# carrier_card_s3.net
KiCad netlist of a schematic drawn in Altium Designer
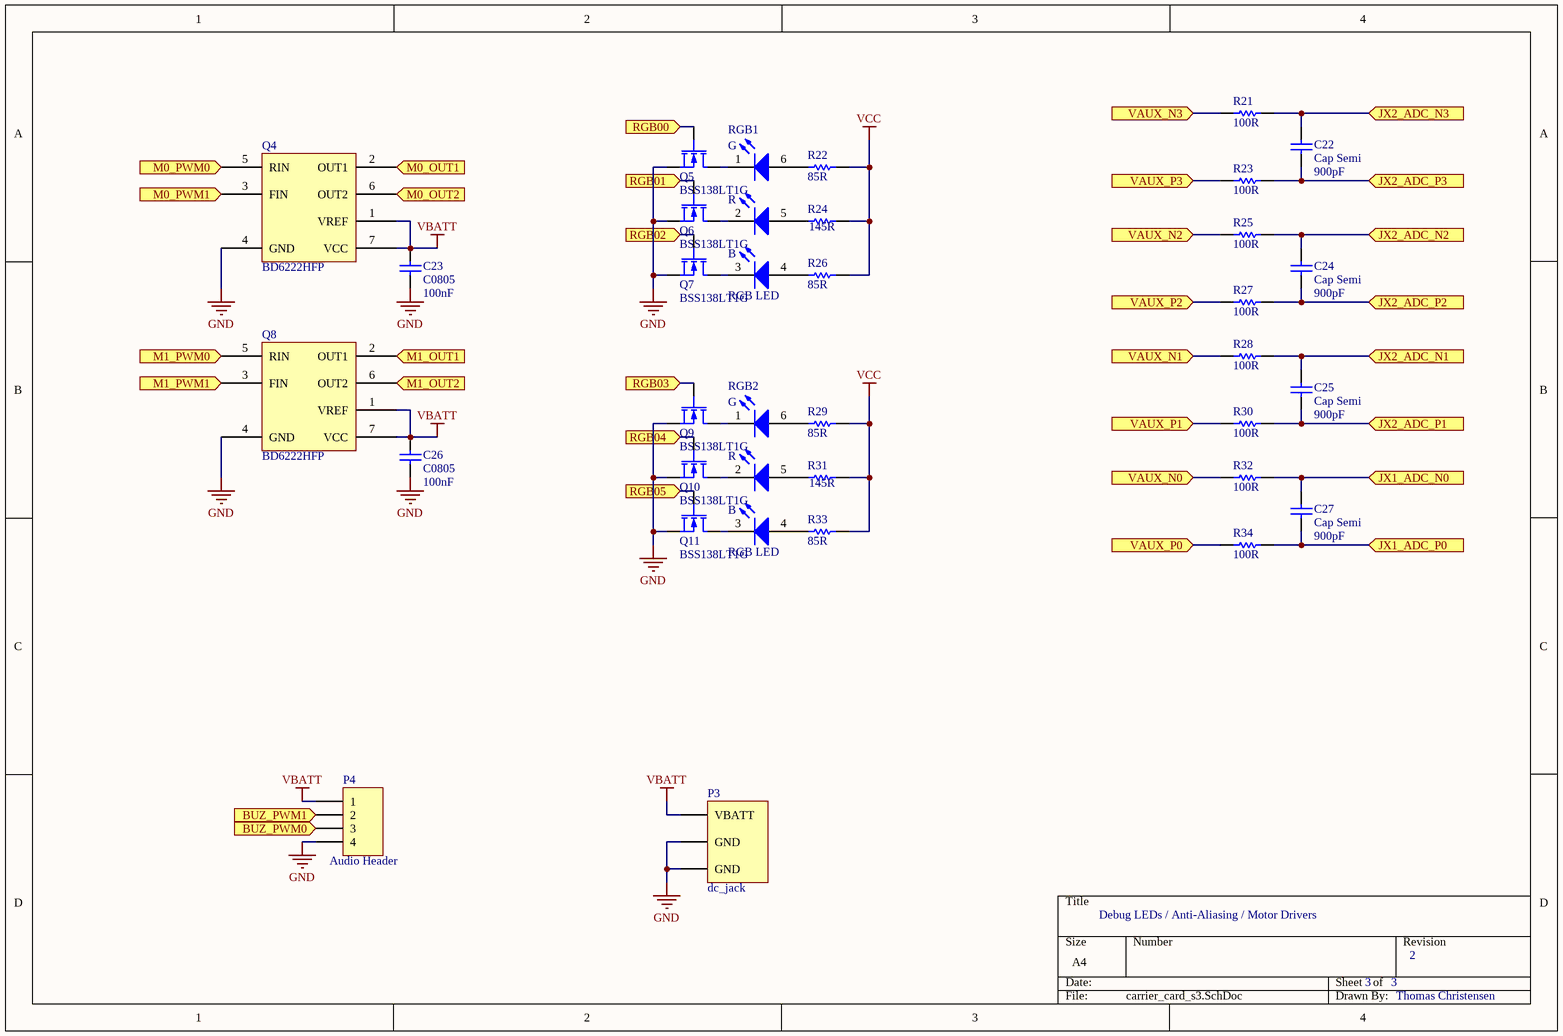
[diagram p0: carrier_card_s3.SchDoc]

(export (version "E")
  (design (tool "Eeschema 10.0.6"))
  (components
    (comp (ref "C22")
      (value "Cap Semi")
      (footprint "0402")
      (description "Capacitor (Semiconductor SIM Model)")
      (fields (field (name "ALTIUM_VALUE") "900pF") (field (name "PUBLISHER") "Altium Limited"))
      (libsource (lib "Miscellaneous Devices") (part "Cap Semi"))
    )
    (comp (ref "C23")
      (value "C0805")
      (footprint "0805")
      (description "Ceramic Chip Capacitor - Standard")
      (fields (field (name "ALTIUM_VALUE") "100nF") (field (name "PUBLISHER") "Altium Limited"))
      (libsource (lib "KEMET Chip Capacitor") (part "C0805"))
    )
    (comp (ref "C24")
      (value "Cap Semi")
      (footprint "0402")
      (description "Capacitor (Semiconductor SIM Model)")
      (fields (field (name "ALTIUM_VALUE") "900pF") (field (name "PUBLISHER") "Altium Limited"))
      (libsource (lib "Miscellaneous Devices") (part "Cap Semi"))
    )
    (comp (ref "C25")
      (value "Cap Semi")
      (footprint "0402")
      (description "Capacitor (Semiconductor SIM Model)")
      (fields (field (name "ALTIUM_VALUE") "900pF") (field (name "PUBLISHER") "Altium Limited"))
      (libsource (lib "Miscellaneous Devices") (part "Cap Semi"))
    )
    (comp (ref "C26")
      (value "C0805")
      (footprint "0805")
      (description "Ceramic Chip Capacitor - Standard")
      (fields (field (name "ALTIUM_VALUE") "100nF") (field (name "PUBLISHER") "Altium Limited"))
      (libsource (lib "KEMET Chip Capacitor") (part "C0805"))
    )
    (comp (ref "C27")
      (value "Cap Semi")
      (footprint "0402")
      (description "Capacitor (Semiconductor SIM Model)")
      (fields (field (name "ALTIUM_VALUE") "900pF") (field (name "PUBLISHER") "Altium Limited"))
      (libsource (lib "Miscellaneous Devices") (part "Cap Semi"))
    )
    (comp (ref "P3")
      (value "dc_jack")
      (footprint "Power Jack")
      (libsource (lib "swarmbot_schematic_library") (part "dc_jack"))
    )
    (comp (ref "P4")
      (value "Audio Header")
      (footprint "HDR1X4")
      (description "Header, 4-Pin")
      (fields (field (name "PUBLISHER") "Altium Limited"))
      (libsource (lib "Miscellaneous Connectors") (part "Header 4"))
    )
    (comp (ref "Q4")
      (value "BD6222HFP")
      (footprint "HRP7_N")
      (libsource (lib "swarmbot_schematic_library") (part "BD6222HFP"))
    )
    (comp (ref "Q5")
      (value "BSS138LT1G")
      (footprint "SOT-23B")
      (description "N-Channel MOSFET")
      (fields (field (name "PUBLISHER") "Altium Limited"))
      (libsource (lib "swarmbot_schematic_library") (part "BSS138LT1G"))
    )
    (comp (ref "Q6")
      (value "BSS138LT1G")
      (footprint "SOT-23B")
      (description "N-Channel MOSFET")
      (fields (field (name "PUBLISHER") "Altium Limited"))
      (libsource (lib "swarmbot_schematic_library") (part "BSS138LT1G"))
    )
    (comp (ref "Q7")
      (value "BSS138LT1G")
      (footprint "SOT-23B")
      (description "N-Channel MOSFET")
      (fields (field (name "PUBLISHER") "Altium Limited"))
      (libsource (lib "swarmbot_schematic_library") (part "BSS138LT1G"))
    )
    (comp (ref "Q8")
      (value "BD6222HFP")
      (footprint "HRP7_N")
      (libsource (lib "swarmbot_schematic_library") (part "BD6222HFP"))
    )
    (comp (ref "Q9")
      (value "BSS138LT1G")
      (footprint "SOT-23B")
      (description "N-Channel MOSFET")
      (fields (field (name "PUBLISHER") "Altium Limited"))
      (libsource (lib "swarmbot_schematic_library") (part "BSS138LT1G"))
    )
    (comp (ref "Q10")
      (value "BSS138LT1G")
      (footprint "SOT-23B")
      (description "N-Channel MOSFET")
      (fields (field (name "PUBLISHER") "Altium Limited"))
      (libsource (lib "swarmbot_schematic_library") (part "BSS138LT1G"))
    )
    (comp (ref "Q11")
      (value "BSS138LT1G")
      (footprint "SOT-23B")
      (description "N-Channel MOSFET")
      (fields (field (name "PUBLISHER") "Altium Limited"))
      (libsource (lib "swarmbot_schematic_library") (part "BSS138LT1G"))
    )
    (comp (ref "R21")
      (value "100R")
      (footprint "2-0402")
      (description "Thick Film Chip Resistor, 1 Ohm to 2.2M Ohm Range, 5% Tolerance, 0402 Size, 0.063 W")
      (fields (field (name "PUBLISHER") "Altium Limited"))
      (libsource (lib "Panasonic Resistor") (part "ERJ2GE"))
    )
    (comp (ref "R22")
      (value "85R")
      (footprint "ERA-0603")
      (fields (field (name "PUBLISHER") "Altium Limited"))
      (libsource (lib "Panasonic Resistor") (part "ERA3Y"))
    )
    (comp (ref "R23")
      (value "100R")
      (footprint "2-0402")
      (description "Thick Film Chip Resistor, 1 Ohm to 2.2M Ohm Range, 5% Tolerance, 0402 Size, 0.063 W")
      (fields (field (name "PUBLISHER") "Altium Limited"))
      (libsource (lib "Panasonic Resistor") (part "ERJ2GE"))
    )
    (comp (ref "R24")
      (value "145R")
      (footprint "ERA-0603")
      (fields (field (name "PUBLISHER") "Altium Limited"))
      (libsource (lib "Panasonic Resistor") (part "ERA3Y"))
    )
    (comp (ref "R25")
      (value "100R")
      (footprint "2-0402")
      (description "Thick Film Chip Resistor, 1 Ohm to 2.2M Ohm Range, 5% Tolerance, 0402 Size, 0.063 W")
      (fields (field (name "PUBLISHER") "Altium Limited"))
      (libsource (lib "Panasonic Resistor") (part "ERJ2GE"))
    )
    (comp (ref "R26")
      (value "85R")
      (footprint "ERA-0603")
      (fields (field (name "PUBLISHER") "Altium Limited"))
      (libsource (lib "Panasonic Resistor") (part "ERA3Y"))
    )
    (comp (ref "R27")
      (value "100R")
      (footprint "2-0402")
      (description "Thick Film Chip Resistor, 1 Ohm to 2.2M Ohm Range, 5% Tolerance, 0402 Size, 0.063 W")
      (fields (field (name "PUBLISHER") "Altium Limited"))
      (libsource (lib "Panasonic Resistor") (part "ERJ2GE"))
    )
    (comp (ref "R28")
      (value "100R")
      (footprint "2-0402")
      (description "Thick Film Chip Resistor, 1 Ohm to 2.2M Ohm Range, 5% Tolerance, 0402 Size, 0.063 W")
      (fields (field (name "PUBLISHER") "Altium Limited"))
      (libsource (lib "Panasonic Resistor") (part "ERJ2GE"))
    )
    (comp (ref "R29")
      (value "85R")
      (footprint "ERA-0603")
      (fields (field (name "PUBLISHER") "Altium Limited"))
      (libsource (lib "Panasonic Resistor") (part "ERA3Y"))
    )
    (comp (ref "R30")
      (value "100R")
      (footprint "2-0402")
      (description "Thick Film Chip Resistor, 1 Ohm to 2.2M Ohm Range, 5% Tolerance, 0402 Size, 0.063 W")
      (fields (field (name "PUBLISHER") "Altium Limited"))
      (libsource (lib "Panasonic Resistor") (part "ERJ2GE"))
    )
    (comp (ref "R31")
      (value "145R")
      (footprint "ERA-0603")
      (fields (field (name "PUBLISHER") "Altium Limited"))
      (libsource (lib "Panasonic Resistor") (part "ERA3Y"))
    )
    (comp (ref "R32")
      (value "100R")
      (footprint "2-0402")
      (description "Thick Film Chip Resistor, 1 Ohm to 2.2M Ohm Range, 5% Tolerance, 0402 Size, 0.063 W")
      (fields (field (name "PUBLISHER") "Altium Limited"))
      (libsource (lib "Panasonic Resistor") (part "ERJ2GE"))
    )
    (comp (ref "R33")
      (value "85R")
      (footprint "ERA-0603")
      (fields (field (name "PUBLISHER") "Altium Limited"))
      (libsource (lib "Panasonic Resistor") (part "ERA3Y"))
    )
    (comp (ref "R34")
      (value "100R")
      (footprint "2-0402")
      (description "Thick Film Chip Resistor, 1 Ohm to 2.2M Ohm Range, 5% Tolerance, 0402 Size, 0.063 W")
      (fields (field (name "PUBLISHER") "Altium Limited"))
      (libsource (lib "Panasonic Resistor") (part "ERJ2GE"))
    )
    (comp (ref "RGB1")
      (value "RGB LED")
      (footprint "RGB_LED")
      (libsource (lib "swarmbot_schematic_library") (part "LTRB R8SF"))
    )
    (comp (ref "RGB2")
      (value "RGB LED")
      (footprint "RGB_LED")
      (libsource (lib "swarmbot_schematic_library") (part "LTRB R8SF"))
    )
  )
  (nets
    (net (code "1") (name "/BUZ_PWM0") (class "Default")
      (node (ref "P4") (pin "3") (pinfunction "3_3") (pintype "passive"))
    )
    (net (code "2") (name "/BUZ_PWM1") (class "Default")
      (node (ref "P4") (pin "2") (pinfunction "2_2") (pintype "passive"))
    )
    (net (code "3") (name "/JX1_ADC_N0") (class "Default")
      (node (ref "C27") (pin "2") (pinfunction "2_2") (pintype "passive"))
      (node (ref "R32") (pin "2") (pinfunction "2_2") (pintype "passive"))
    )
    (net (code "4") (name "/JX1_ADC_P0") (class "Default")
      (node (ref "C27") (pin "1") (pinfunction "1_1") (pintype "passive"))
      (node (ref "R34") (pin "2") (pinfunction "2_2") (pintype "passive"))
    )
    (net (code "5") (name "/JX2_ADC_N1") (class "Default")
      (node (ref "C25") (pin "2") (pinfunction "2_2") (pintype "passive"))
      (node (ref "R28") (pin "2") (pinfunction "2_2") (pintype "passive"))
    )
    (net (code "6") (name "/JX2_ADC_N2") (class "Default")
      (node (ref "C24") (pin "2") (pinfunction "2_2") (pintype "passive"))
      (node (ref "R25") (pin "2") (pinfunction "2_2") (pintype "passive"))
    )
    (net (code "7") (name "/JX2_ADC_N3") (class "Default")
      (node (ref "C22") (pin "2") (pinfunction "2_2") (pintype "passive"))
      (node (ref "R21") (pin "2") (pinfunction "2_2") (pintype "passive"))
    )
    (net (code "8") (name "/JX2_ADC_P1") (class "Default")
      (node (ref "C25") (pin "1") (pinfunction "1_1") (pintype "passive"))
      (node (ref "R30") (pin "2") (pinfunction "2_2") (pintype "passive"))
    )
    (net (code "9") (name "/JX2_ADC_P2") (class "Default")
      (node (ref "C24") (pin "1") (pinfunction "1_1") (pintype "passive"))
      (node (ref "R27") (pin "2") (pinfunction "2_2") (pintype "passive"))
    )
    (net (code "10") (name "/JX2_ADC_P3") (class "Default")
      (node (ref "C22") (pin "1") (pinfunction "1_1") (pintype "passive"))
      (node (ref "R23") (pin "2") (pinfunction "2_2") (pintype "passive"))
    )
    (net (code "11") (name "/M0_OUT1") (class "Default")
      (node (ref "Q4") (pin "2") (pinfunction "OUT1_2") (pintype "passive"))
    )
    (net (code "12") (name "/M0_OUT2") (class "Default")
      (node (ref "Q4") (pin "6") (pinfunction "OUT2_6") (pintype "passive"))
    )
    (net (code "13") (name "/M0_PWM0") (class "Default")
      (node (ref "Q4") (pin "5") (pinfunction "RIN_5") (pintype "passive"))
    )
    (net (code "14") (name "/M0_PWM1") (class "Default")
      (node (ref "Q4") (pin "3") (pinfunction "FIN_3") (pintype "passive"))
    )
    (net (code "15") (name "/M1_OUT1") (class "Default")
      (node (ref "Q8") (pin "2") (pinfunction "OUT1_2") (pintype "passive"))
    )
    (net (code "16") (name "/M1_OUT2") (class "Default")
      (node (ref "Q8") (pin "6") (pinfunction "OUT2_6") (pintype "passive"))
    )
    (net (code "17") (name "/M1_PWM0") (class "Default")
      (node (ref "Q8") (pin "5") (pinfunction "RIN_5") (pintype "passive"))
    )
    (net (code "18") (name "/M1_PWM1") (class "Default")
      (node (ref "Q8") (pin "3") (pinfunction "FIN_3") (pintype "passive"))
    )
    (net (code "19") (name "/RGB00") (class "Default")
      (node (ref "Q5") (pin "1") (pinfunction "G_1") (pintype "passive"))
    )
    (net (code "20") (name "/RGB01") (class "Default")
      (node (ref "Q6") (pin "1") (pinfunction "G_1") (pintype "passive"))
    )
    (net (code "21") (name "/RGB02") (class "Default")
      (node (ref "Q7") (pin "1") (pinfunction "G_1") (pintype "passive"))
    )
    (net (code "22") (name "/RGB03") (class "Default")
      (node (ref "Q9") (pin "1") (pinfunction "G_1") (pintype "passive"))
    )
    (net (code "23") (name "/RGB04") (class "Default")
      (node (ref "Q10") (pin "1") (pinfunction "G_1") (pintype "passive"))
    )
    (net (code "24") (name "/RGB05") (class "Default")
      (node (ref "Q11") (pin "1") (pinfunction "G_1") (pintype "passive"))
    )
    (net (code "25") (name "/VAUX_N0") (class "Default")
      (node (ref "R32") (pin "1") (pinfunction "1_1") (pintype "passive"))
    )
    (net (code "26") (name "/VAUX_N1") (class "Default")
      (node (ref "R28") (pin "1") (pinfunction "1_1") (pintype "passive"))
    )
    (net (code "27") (name "/VAUX_N2") (class "Default")
      (node (ref "R25") (pin "1") (pinfunction "1_1") (pintype "passive"))
    )
    (net (code "28") (name "/VAUX_N3") (class "Default")
      (node (ref "R21") (pin "1") (pinfunction "1_1") (pintype "passive"))
    )
    (net (code "29") (name "/VAUX_P0") (class "Default")
      (node (ref "R34") (pin "1") (pinfunction "1_1") (pintype "passive"))
    )
    (net (code "30") (name "/VAUX_P1") (class "Default")
      (node (ref "R30") (pin "1") (pinfunction "1_1") (pintype "passive"))
    )
    (net (code "31") (name "/VAUX_P2") (class "Default")
      (node (ref "R27") (pin "1") (pinfunction "1_1") (pintype "passive"))
    )
    (net (code "32") (name "/VAUX_P3") (class "Default")
      (node (ref "R23") (pin "1") (pinfunction "1_1") (pintype "passive"))
    )
    (net (code "33") (name "GND") (class "Default")
      (node (ref "C23") (pin "1") (pinfunction "1_1") (pintype "passive"))
      (node (ref "C26") (pin "1") (pinfunction "1_1") (pintype "passive"))
      (node (ref "P3") (pin "2") (pinfunction "GND_2") (pintype "passive"))
      (node (ref "P3") (pin "3") (pinfunction "GND_3") (pintype "passive"))
      (node (ref "P4") (pin "4") (pinfunction "4_4") (pintype "passive"))
      (node (ref "Q10") (pin "2") (pinfunction "S_2") (pintype "passive"))
      (node (ref "Q11") (pin "2") (pinfunction "S_2") (pintype "passive"))
      (node (ref "Q4") (pin "4") (pinfunction "GND_4") (pintype "passive"))
      (node (ref "Q5") (pin "2") (pinfunction "S_2") (pintype "passive"))
      (node (ref "Q6") (pin "2") (pinfunction "S_2") (pintype "passive"))
      (node (ref "Q7") (pin "2") (pinfunction "S_2") (pintype "passive"))
      (node (ref "Q8") (pin "4") (pinfunction "GND_4") (pintype "passive"))
      (node (ref "Q9") (pin "2") (pinfunction "S_2") (pintype "passive"))
    )
    (net (code "34") (name "Net-(Q5-D)") (class "Default")
      (node (ref "Q5") (pin "3") (pinfunction "D_3") (pintype "passive"))
      (node (ref "RGB1") (pin "1") (pinfunction "1_1") (pintype "passive"))
    )
    (net (code "35") (name "Net-(Q6-D)") (class "Default")
      (node (ref "Q6") (pin "3") (pinfunction "D_3") (pintype "passive"))
      (node (ref "RGB1") (pin "2") (pinfunction "2_2") (pintype "passive"))
    )
    (net (code "36") (name "Net-(Q7-D)") (class "Default")
      (node (ref "Q7") (pin "3") (pinfunction "D_3") (pintype "passive"))
      (node (ref "RGB1") (pin "3") (pinfunction "3_3") (pintype "passive"))
    )
    (net (code "37") (name "Net-(Q9-D)") (class "Default")
      (node (ref "Q9") (pin "3") (pinfunction "D_3") (pintype "passive"))
      (node (ref "RGB2") (pin "1") (pinfunction "1_1") (pintype "passive"))
    )
    (net (code "38") (name "Net-(Q10-D)") (class "Default")
      (node (ref "Q10") (pin "3") (pinfunction "D_3") (pintype "passive"))
      (node (ref "RGB2") (pin "2") (pinfunction "2_2") (pintype "passive"))
    )
    (net (code "39") (name "Net-(Q11-D)") (class "Default")
      (node (ref "Q11") (pin "3") (pinfunction "D_3") (pintype "passive"))
      (node (ref "RGB2") (pin "3") (pinfunction "3_3") (pintype "passive"))
    )
    (net (code "40") (name "Net-(R22-Pad1)") (class "Default")
      (node (ref "R22") (pin "1") (pinfunction "1_1") (pintype "passive"))
      (node (ref "RGB1") (pin "6") (pinfunction "6_6") (pintype "passive"))
    )
    (net (code "41") (name "Net-(R24-Pad1)") (class "Default")
      (node (ref "R24") (pin "1") (pinfunction "1_1") (pintype "passive"))
      (node (ref "RGB1") (pin "5") (pinfunction "5_5") (pintype "passive"))
    )
    (net (code "42") (name "Net-(R26-Pad1)") (class "Default")
      (node (ref "R26") (pin "1") (pinfunction "1_1") (pintype "passive"))
      (node (ref "RGB1") (pin "4") (pinfunction "4_4") (pintype "passive"))
    )
    (net (code "43") (name "Net-(R29-Pad1)") (class "Default")
      (node (ref "R29") (pin "1") (pinfunction "1_1") (pintype "passive"))
      (node (ref "RGB2") (pin "6") (pinfunction "6_6") (pintype "passive"))
    )
    (net (code "44") (name "Net-(R31-Pad1)") (class "Default")
      (node (ref "R31") (pin "1") (pinfunction "1_1") (pintype "passive"))
      (node (ref "RGB2") (pin "5") (pinfunction "5_5") (pintype "passive"))
    )
    (net (code "45") (name "Net-(R33-Pad1)") (class "Default")
      (node (ref "R33") (pin "1") (pinfunction "1_1") (pintype "passive"))
      (node (ref "RGB2") (pin "4") (pinfunction "4_4") (pintype "passive"))
    )
    (net (code "46") (name "VBATT") (class "Default")
      (node (ref "C23") (pin "2") (pinfunction "2_2") (pintype "passive"))
      (node (ref "C26") (pin "2") (pinfunction "2_2") (pintype "passive"))
      (node (ref "P3") (pin "1") (pinfunction "VBATT_1") (pintype "passive"))
      (node (ref "P4") (pin "1") (pinfunction "1_1") (pintype "passive"))
      (node (ref "Q4") (pin "1") (pinfunction "VREF_1") (pintype "passive"))
      (node (ref "Q4") (pin "7") (pinfunction "VCC_7") (pintype "passive"))
      (node (ref "Q8") (pin "1") (pinfunction "VREF_1") (pintype "passive"))
      (node (ref "Q8") (pin "7") (pinfunction "VCC_7") (pintype "passive"))
    )
    (net (code "47") (name "VCC") (class "Default")
      (node (ref "R22") (pin "2") (pinfunction "2_2") (pintype "passive"))
      (node (ref "R24") (pin "2") (pinfunction "2_2") (pintype "passive"))
      (node (ref "R26") (pin "2") (pinfunction "2_2") (pintype "passive"))
      (node (ref "R29") (pin "2") (pinfunction "2_2") (pintype "passive"))
      (node (ref "R31") (pin "2") (pinfunction "2_2") (pintype "passive"))
      (node (ref "R33") (pin "2") (pinfunction "2_2") (pintype "passive"))
    )
  )
)
